# DHT_Board-v_1_2.net
KiCad netlist of a schematic drawn in EAGLE
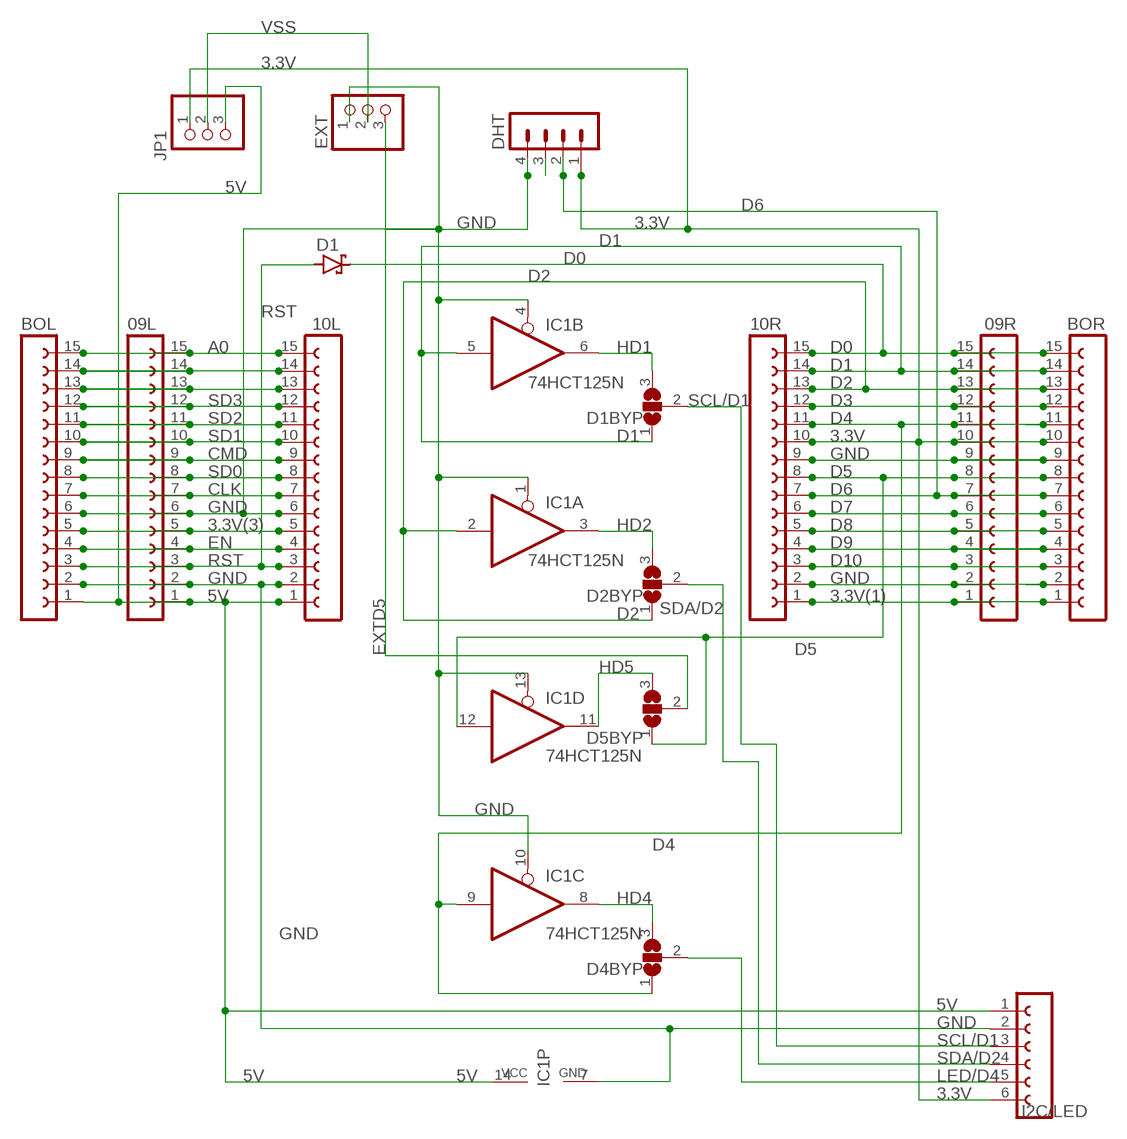
[diagram p0: schematic, sheet 1]

(export (version "E")
  (design (tool "Eeschema 10.0.6"))
  (components
    (comp (ref "09L")
      (value "15")
      (footprint "eagle-import:FE15")
      (libsource (lib "eagle-import") (part "FE15-1"))
    )
    (comp (ref "09R")
      (value "15")
      (footprint "eagle-import:FE15")
      (libsource (lib "eagle-import") (part "FE15-1"))
    )
    (comp (ref "10L")
      (value "15")
      (footprint "eagle-import:FE15")
      (libsource (lib "eagle-import") (part "FE15-1"))
    )
    (comp (ref "10R")
      (value "15")
      (footprint "eagle-import:FE15")
      (libsource (lib "eagle-import") (part "FE15-1"))
    )
    (comp (ref "BOL")
      (value "15")
      (footprint "eagle-import:FE15")
      (libsource (lib "eagle-import") (part "FE15-1"))
    )
    (comp (ref "BOR")
      (value "15")
      (footprint "eagle-import:FE15")
      (libsource (lib "eagle-import") (part "FE15-1"))
    )
    (comp (ref "D1")
      (value "BAT43")
      (footprint "eagle-import:DO35-10")
      (libsource (lib "eagle-import") (part "BAT42"))
    )
    (comp (ref "D1BYP")
      (value "SJ2W")
      (footprint "eagle-import:SJ_2")
      (libsource (lib "eagle-import") (part "SJ2W"))
    )
    (comp (ref "D2BYP")
      (value "SJ2W")
      (footprint "eagle-import:SJ_2")
      (libsource (lib "eagle-import") (part "SJ2W"))
    )
    (comp (ref "D4BYP")
      (value "SJ2W")
      (footprint "eagle-import:SJ_2")
      (libsource (lib "eagle-import") (part "SJ2W"))
    )
    (comp (ref "D5BYP")
      (value "SJ2W")
      (footprint "eagle-import:SJ_2")
      (libsource (lib "eagle-import") (part "SJ2W"))
    )
    (comp (ref "DHT")
      (value "MA04-1")
      (footprint "eagle-import:MA04-1")
      (libsource (lib "eagle-import") (part "MA04-1"))
    )
    (comp (ref "EXT")
      (value "PINHD-1X3/90")
      (footprint "eagle-import:1X03_90")
      (libsource (lib "eagle-import") (part "PINHD-1X3/90"))
    )
    (comp (ref "I2C/LED")
      (value "FE06-1")
      (footprint "eagle-import:FE06")
      (libsource (lib "eagle-import") (part "FE06-1"))
    )
    (comp (ref "IC1")
      (value "74HCT125N")
      (footprint "eagle-import:DIL14")
      (libsource (lib "eagle-import") (part "74125NHCT"))
    )
    (comp (ref "JP1")
      (value "PINHD-1X3")
      (footprint "eagle-import:1X03")
      (libsource (lib "eagle-import") (part "PINHD-1X3"))
    )
  )
  (nets
    (net (code "1") (name "/3.3V") (class "Default")
      (node (ref "09R") (pin "10") (pinfunction "10_10") (pintype "passive"))
      (node (ref "10R") (pin "10") (pinfunction "10_10") (pintype "passive"))
      (node (ref "BOR") (pin "10") (pinfunction "10_10") (pintype "passive"))
      (node (ref "DHT") (pin "1") (pinfunction "1_1") (pintype "passive"))
      (node (ref "I2C/LED") (pin "6") (pinfunction "6_6") (pintype "passive"))
      (node (ref "JP1") (pin "1") (pinfunction "1_1") (pintype "passive"))
    )
    (net (code "2") (name "/3.3V(1)") (class "Default")
      (node (ref "09R") (pin "1") (pinfunction "1_1") (pintype "passive"))
      (node (ref "10R") (pin "1") (pinfunction "1_1") (pintype "passive"))
      (node (ref "BOR") (pin "1") (pinfunction "1_1") (pintype "passive"))
    )
    (net (code "3") (name "/3.3V(3)") (class "Default")
      (node (ref "09L") (pin "5") (pinfunction "5_5") (pintype "passive"))
      (node (ref "10L") (pin "5") (pinfunction "5_5") (pintype "passive"))
      (node (ref "BOL") (pin "5") (pinfunction "5_5") (pintype "passive"))
    )
    (net (code "4") (name "/5V") (class "Default")
      (node (ref "09L") (pin "1") (pinfunction "1_1") (pintype "passive"))
      (node (ref "10L") (pin "1") (pinfunction "1_1") (pintype "passive"))
      (node (ref "BOL") (pin "1") (pinfunction "1_1") (pintype "passive"))
      (node (ref "I2C/LED") (pin "1") (pinfunction "1_1") (pintype "passive"))
      (node (ref "IC1") (pin "14") (pinfunction "VCC_14") (pintype "power_in"))
      (node (ref "JP1") (pin "3") (pinfunction "3_3") (pintype "passive"))
    )
    (net (code "5") (name "/A0") (class "Default")
      (node (ref "09L") (pin "15") (pinfunction "15_15") (pintype "passive"))
      (node (ref "10L") (pin "15") (pinfunction "15_15") (pintype "passive"))
      (node (ref "BOL") (pin "15") (pinfunction "15_15") (pintype "passive"))
    )
    (net (code "6") (name "/CLK") (class "Default")
      (node (ref "09L") (pin "7") (pinfunction "7_7") (pintype "passive"))
      (node (ref "10L") (pin "7") (pinfunction "7_7") (pintype "passive"))
      (node (ref "BOL") (pin "7") (pinfunction "7_7") (pintype "passive"))
    )
    (net (code "7") (name "/CMD") (class "Default")
      (node (ref "09L") (pin "9") (pinfunction "9_9") (pintype "passive"))
      (node (ref "10L") (pin "9") (pinfunction "9_9") (pintype "passive"))
      (node (ref "BOL") (pin "9") (pinfunction "9_9") (pintype "passive"))
    )
    (net (code "8") (name "/D0") (class "Default")
      (node (ref "09R") (pin "15") (pinfunction "15_15") (pintype "passive"))
      (node (ref "10R") (pin "15") (pinfunction "15_15") (pintype "passive"))
      (node (ref "BOR") (pin "15") (pinfunction "15_15") (pintype "passive"))
      (node (ref "D1") (pin "C") (pinfunction "C_C") (pintype "passive"))
    )
    (net (code "9") (name "/D1") (class "Default")
      (node (ref "09R") (pin "14") (pinfunction "14_14") (pintype "passive"))
      (node (ref "10R") (pin "14") (pinfunction "14_14") (pintype "passive"))
      (node (ref "BOR") (pin "14") (pinfunction "14_14") (pintype "passive"))
      (node (ref "D1BYP") (pin "1") (pinfunction "1_1") (pintype "passive"))
      (node (ref "IC1") (pin "5") (pinfunction "I_5") (pintype "input"))
    )
    (net (code "10") (name "/D2") (class "Default")
      (node (ref "09R") (pin "13") (pinfunction "13_13") (pintype "passive"))
      (node (ref "10R") (pin "13") (pinfunction "13_13") (pintype "passive"))
      (node (ref "BOR") (pin "13") (pinfunction "13_13") (pintype "passive"))
      (node (ref "D2BYP") (pin "1") (pinfunction "1_1") (pintype "passive"))
      (node (ref "IC1") (pin "2") (pinfunction "I_2") (pintype "input"))
    )
    (net (code "11") (name "/D3") (class "Default")
      (node (ref "09R") (pin "12") (pinfunction "12_12") (pintype "passive"))
      (node (ref "10R") (pin "12") (pinfunction "12_12") (pintype "passive"))
      (node (ref "BOR") (pin "12") (pinfunction "12_12") (pintype "passive"))
    )
    (net (code "12") (name "/D4") (class "Default")
      (node (ref "09R") (pin "11") (pinfunction "11_11") (pintype "passive"))
      (node (ref "10R") (pin "11") (pinfunction "11_11") (pintype "passive"))
      (node (ref "BOR") (pin "11") (pinfunction "11_11") (pintype "passive"))
      (node (ref "D4BYP") (pin "1") (pinfunction "1_1") (pintype "passive"))
      (node (ref "IC1") (pin "9") (pinfunction "I_9") (pintype "input"))
    )
    (net (code "13") (name "/D5") (class "Default")
      (node (ref "09R") (pin "8") (pinfunction "8_8") (pintype "passive"))
      (node (ref "10R") (pin "8") (pinfunction "8_8") (pintype "passive"))
      (node (ref "BOR") (pin "8") (pinfunction "8_8") (pintype "passive"))
      (node (ref "D5BYP") (pin "1") (pinfunction "1_1") (pintype "passive"))
      (node (ref "IC1") (pin "12") (pinfunction "I_12") (pintype "input"))
    )
    (net (code "14") (name "/D6") (class "Default")
      (node (ref "09R") (pin "7") (pinfunction "7_7") (pintype "passive"))
      (node (ref "10R") (pin "7") (pinfunction "7_7") (pintype "passive"))
      (node (ref "BOR") (pin "7") (pinfunction "7_7") (pintype "passive"))
      (node (ref "DHT") (pin "2") (pinfunction "2_2") (pintype "passive"))
    )
    (net (code "15") (name "/D7") (class "Default")
      (node (ref "09R") (pin "6") (pinfunction "6_6") (pintype "passive"))
      (node (ref "10R") (pin "6") (pinfunction "6_6") (pintype "passive"))
      (node (ref "BOR") (pin "6") (pinfunction "6_6") (pintype "passive"))
    )
    (net (code "16") (name "/D8") (class "Default")
      (node (ref "09R") (pin "5") (pinfunction "5_5") (pintype "passive"))
      (node (ref "10R") (pin "5") (pinfunction "5_5") (pintype "passive"))
      (node (ref "BOR") (pin "5") (pinfunction "5_5") (pintype "passive"))
    )
    (net (code "17") (name "/D9") (class "Default")
      (node (ref "09R") (pin "4") (pinfunction "4_4") (pintype "passive"))
      (node (ref "10R") (pin "4") (pinfunction "4_4") (pintype "passive"))
      (node (ref "BOR") (pin "4") (pinfunction "4_4") (pintype "passive"))
    )
    (net (code "18") (name "/D10") (class "Default")
      (node (ref "09R") (pin "3") (pinfunction "3_3") (pintype "passive"))
      (node (ref "10R") (pin "3") (pinfunction "3_3") (pintype "passive"))
      (node (ref "BOR") (pin "3") (pinfunction "3_3") (pintype "passive"))
    )
    (net (code "19") (name "/EN") (class "Default")
      (node (ref "09L") (pin "4") (pinfunction "4_4") (pintype "passive"))
      (node (ref "10L") (pin "4") (pinfunction "4_4") (pintype "passive"))
      (node (ref "BOL") (pin "4") (pinfunction "4_4") (pintype "passive"))
    )
    (net (code "20") (name "/EXTD5") (class "Default")
      (node (ref "D5BYP") (pin "2") (pinfunction "2_2") (pintype "passive"))
      (node (ref "EXT") (pin "3") (pinfunction "3_3") (pintype "passive"))
    )
    (net (code "21") (name "/GND") (class "Default")
      (node (ref "09L") (pin "2") (pinfunction "2_2") (pintype "passive"))
      (node (ref "09L") (pin "6") (pinfunction "6_6") (pintype "passive"))
      (node (ref "09R") (pin "2") (pinfunction "2_2") (pintype "passive"))
      (node (ref "09R") (pin "9") (pinfunction "9_9") (pintype "passive"))
      (node (ref "10L") (pin "2") (pinfunction "2_2") (pintype "passive"))
      (node (ref "10L") (pin "6") (pinfunction "6_6") (pintype "passive"))
      (node (ref "10R") (pin "2") (pinfunction "2_2") (pintype "passive"))
      (node (ref "10R") (pin "9") (pinfunction "9_9") (pintype "passive"))
      (node (ref "BOL") (pin "2") (pinfunction "2_2") (pintype "passive"))
      (node (ref "BOL") (pin "6") (pinfunction "6_6") (pintype "passive"))
      (node (ref "BOR") (pin "2") (pinfunction "2_2") (pintype "passive"))
      (node (ref "BOR") (pin "9") (pinfunction "9_9") (pintype "passive"))
      (node (ref "DHT") (pin "4") (pinfunction "4_4") (pintype "passive"))
      (node (ref "EXT") (pin "1") (pinfunction "1_1") (pintype "passive"))
      (node (ref "I2C/LED") (pin "2") (pinfunction "2_2") (pintype "passive"))
      (node (ref "IC1") (pin "1") (pinfunction "OE_1") (pintype "input"))
      (node (ref "IC1") (pin "10") (pinfunction "OE_10") (pintype "input"))
      (node (ref "IC1") (pin "13") (pinfunction "OE_13") (pintype "input"))
      (node (ref "IC1") (pin "4") (pinfunction "OE_4") (pintype "input"))
      (node (ref "IC1") (pin "7") (pinfunction "GND_7") (pintype "power_in"))
    )
    (net (code "22") (name "/HD1") (class "Default")
      (node (ref "D1BYP") (pin "3") (pinfunction "3_3") (pintype "passive"))
      (node (ref "IC1") (pin "6") (pinfunction "O_6") (pintype "tri_state"))
    )
    (net (code "23") (name "/HD2") (class "Default")
      (node (ref "D2BYP") (pin "3") (pinfunction "3_3") (pintype "passive"))
      (node (ref "IC1") (pin "3") (pinfunction "O_3") (pintype "tri_state"))
    )
    (net (code "24") (name "/HD4") (class "Default")
      (node (ref "D4BYP") (pin "3") (pinfunction "3_3") (pintype "passive"))
      (node (ref "IC1") (pin "8") (pinfunction "O_8") (pintype "tri_state"))
    )
    (net (code "25") (name "/HD5") (class "Default")
      (node (ref "D5BYP") (pin "3") (pinfunction "3_3") (pintype "passive"))
      (node (ref "IC1") (pin "11") (pinfunction "O_11") (pintype "tri_state"))
    )
    (net (code "26") (name "/LED{slash}D4") (class "Default")
      (node (ref "D4BYP") (pin "2") (pinfunction "2_2") (pintype "passive"))
      (node (ref "I2C/LED") (pin "5") (pinfunction "5_5") (pintype "passive"))
    )
    (net (code "27") (name "/RST") (class "Default")
      (node (ref "09L") (pin "3") (pinfunction "3_3") (pintype "passive"))
      (node (ref "10L") (pin "3") (pinfunction "3_3") (pintype "passive"))
      (node (ref "BOL") (pin "3") (pinfunction "3_3") (pintype "passive"))
      (node (ref "D1") (pin "A") (pinfunction "A_A") (pintype "passive"))
    )
    (net (code "28") (name "/SCL{slash}D1") (class "Default")
      (node (ref "D1BYP") (pin "2") (pinfunction "2_2") (pintype "passive"))
      (node (ref "I2C/LED") (pin "3") (pinfunction "3_3") (pintype "passive"))
    )
    (net (code "29") (name "/SD0") (class "Default")
      (node (ref "09L") (pin "8") (pinfunction "8_8") (pintype "passive"))
      (node (ref "10L") (pin "8") (pinfunction "8_8") (pintype "passive"))
      (node (ref "BOL") (pin "8") (pinfunction "8_8") (pintype "passive"))
    )
    (net (code "30") (name "/SD1") (class "Default")
      (node (ref "09L") (pin "10") (pinfunction "10_10") (pintype "passive"))
      (node (ref "10L") (pin "10") (pinfunction "10_10") (pintype "passive"))
      (node (ref "BOL") (pin "10") (pinfunction "10_10") (pintype "passive"))
    )
    (net (code "31") (name "/SD2") (class "Default")
      (node (ref "09L") (pin "11") (pinfunction "11_11") (pintype "passive"))
      (node (ref "10L") (pin "11") (pinfunction "11_11") (pintype "passive"))
      (node (ref "BOL") (pin "11") (pinfunction "11_11") (pintype "passive"))
    )
    (net (code "32") (name "/SD3") (class "Default")
      (node (ref "09L") (pin "12") (pinfunction "12_12") (pintype "passive"))
      (node (ref "10L") (pin "12") (pinfunction "12_12") (pintype "passive"))
      (node (ref "BOL") (pin "12") (pinfunction "12_12") (pintype "passive"))
    )
    (net (code "33") (name "/SDA{slash}D2") (class "Default")
      (node (ref "D2BYP") (pin "2") (pinfunction "2_2") (pintype "passive"))
      (node (ref "I2C/LED") (pin "4") (pinfunction "4_4") (pintype "passive"))
    )
    (net (code "34") (name "/VSS") (class "Default")
      (node (ref "EXT") (pin "2") (pinfunction "2_2") (pintype "passive"))
      (node (ref "JP1") (pin "2") (pinfunction "2_2") (pintype "passive"))
    )
    (net (code "35") (name "Net-(09L-Pad13)") (class "Default")
      (node (ref "09L") (pin "13") (pinfunction "13_13") (pintype "passive"))
      (node (ref "10L") (pin "13") (pinfunction "13_13") (pintype "passive"))
      (node (ref "BOL") (pin "13") (pinfunction "13_13") (pintype "passive"))
    )
    (net (code "36") (name "Net-(09L-Pad14)") (class "Default")
      (node (ref "09L") (pin "14") (pinfunction "14_14") (pintype "passive"))
      (node (ref "10L") (pin "14") (pinfunction "14_14") (pintype "passive"))
      (node (ref "BOL") (pin "14") (pinfunction "14_14") (pintype "passive"))
    )
    (net (code "37") (name "unconnected-(DHT-Pad3)") (class "Default")
      (node (ref "DHT") (pin "3") (pinfunction "3_3") (pintype "passive"))
    )
  )
)
